# MINI-STM32.net
KiCad netlist of a schematic drawn in Altium Designer
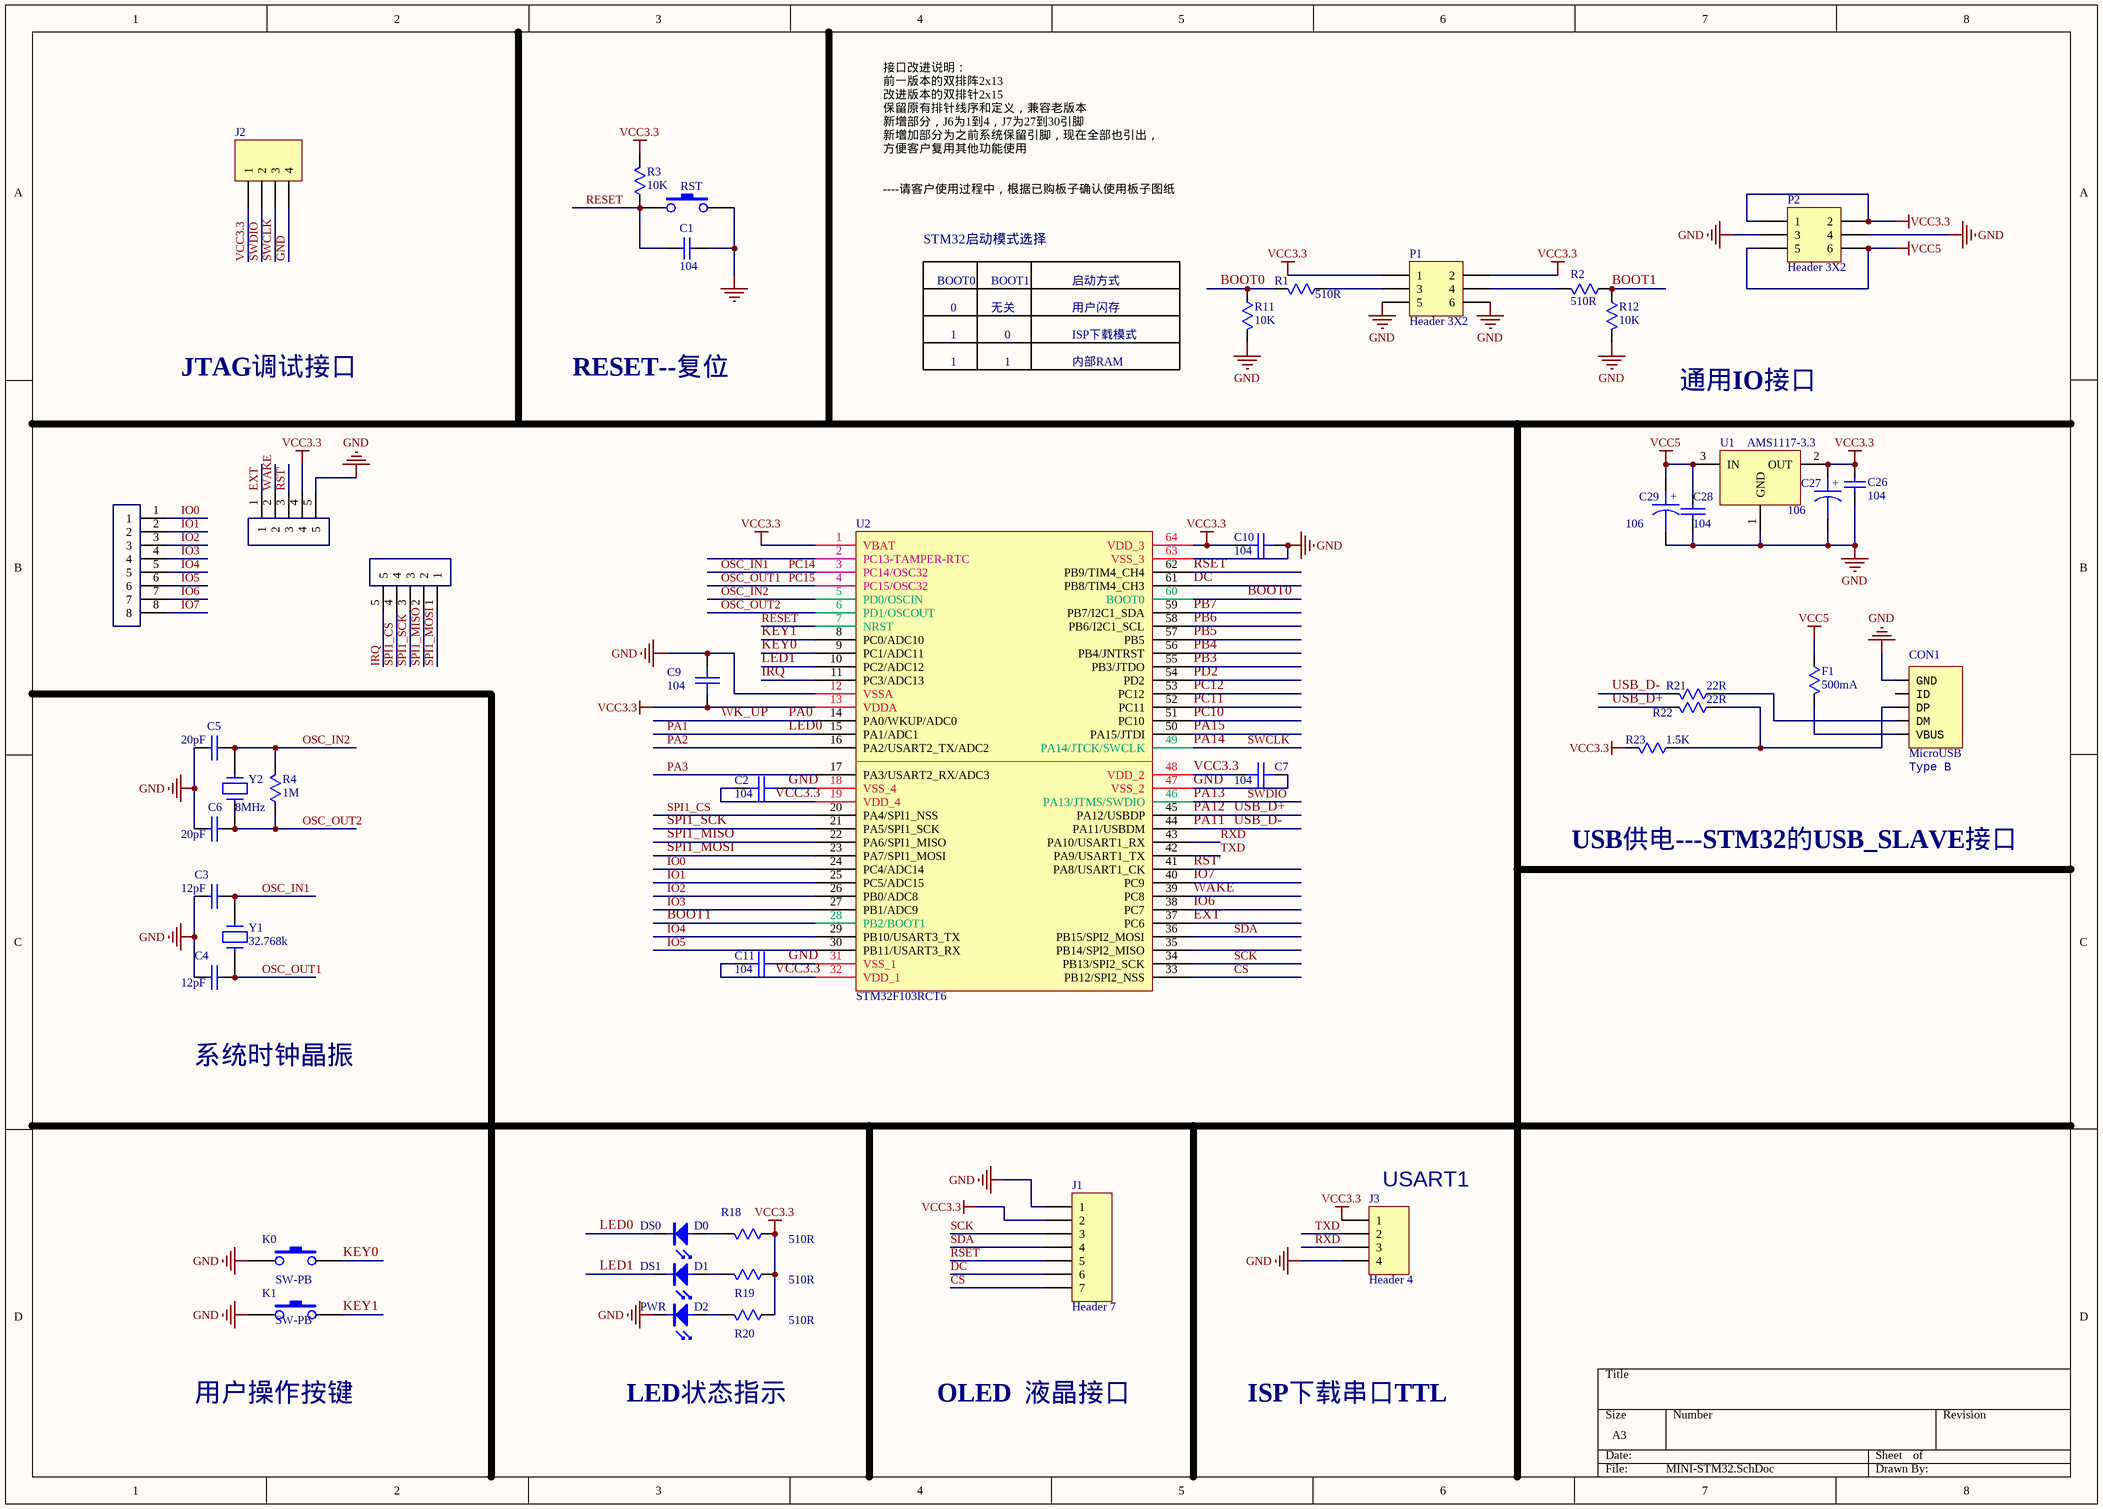
[diagram p0: MINI-STM32.SchDoc]

(export (version "E")
  (design (tool "Eeschema 10.0.6"))
  (components
    (comp (ref "C1")
      (value "104")
      (footprint "0603C")
      (description "GRM39 X7R102K50PT")
      (fields (field (name "PUBLISHER") "Altium Limited"))
      (libsource (lib "") (part "CAP_1"))
    )
    (comp (ref "C2") (value "104") (footprint "0603J") (libsource (lib "YT1_SCH_99SE") (part "CAP")))
    (comp (ref "C3")
      (value "12pF")
      (footprint "0603J")
      (description "CAP CHIP 20P 50V(+-5% C0G 0603)")
      (libsource (lib "Miscellaneous Devices") (part "CAP"))
    )
    (comp (ref "C4")
      (value "12pF")
      (footprint "0603J")
      (description "CAP CHIP 20P 50V(+-5% C0G 0603)")
      (libsource (lib "Miscellaneous Devices") (part "CAP"))
    )
    (comp (ref "C5")
      (value "20pF")
      (footprint "0603J")
      (description "CAP CHIP 20P 50V(+-5% C0G 0603)")
      (libsource (lib "Miscellaneous Devices") (part "CAP"))
    )
    (comp (ref "C6")
      (value "20pF")
      (footprint "0603J")
      (description "CAP CHIP 20P 50V(+-5% C0G 0603)")
      (libsource (lib "Miscellaneous Devices") (part "CAP"))
    )
    (comp (ref "C7") (value "104") (footprint "0603J") (libsource (lib "YT1_SCH_99SE") (part "CAP")))
    (comp (ref "C9") (value "104") (footprint "0603J") (libsource (lib "YT1_SCH_99SE") (part "CAP")))
    (comp (ref "C10") (value "104") (footprint "0603J") (libsource (lib "YT1_SCH_99SE") (part "CAP")))
    (comp (ref "C11") (value "104") (footprint "0603J") (libsource (lib "YT1_SCH_99SE") (part "CAP")))
    (comp (ref "C26")
      (value "104")
      (footprint "0603J")
      (description "Capacitor")
      (fields (field (name "PUBLISHER") "Altium Limited"))
      (libsource (lib "*") (part "Cap"))
    )
    (comp (ref "C27")
      (value "106")
      (footprint "RC0805")
      (description "Capacitor")
      (libsource (lib "*") (part "CAPACITOR POL"))
    )
    (comp (ref "C28")
      (value "104")
      (footprint "0603J")
      (description "Capacitor")
      (libsource (lib "*") (part "CAP"))
    )
    (comp (ref "C29")
      (value "106")
      (footprint "RC0805")
      (description "Capacitor")
      (libsource (lib "*") (part "CAPACITOR POL"))
    )
    (comp (ref "CON1")
      (value "MicroUSB")
      (footprint "PCB_USB:USB_Micro-AB")
      (description "USB")
      (fields (field (name "ALTIUM_VALUE") "Type B"))
      (libsource (lib "SCH_USB") (part "USB_Micro"))
    )
    (comp (ref "D0") (value "DS0") (footprint "LED0805") (libsource (lib "YT1_SCH_99SE") (part "LED")))
    (comp (ref "D1") (value "DS1") (footprint "LED0805") (libsource (lib "YT1_SCH_99SE") (part "LED")))
    (comp (ref "D2") (value "PWR") (footprint "LED0805") (libsource (lib "YT1_SCH_99SE") (part "LED")))
    (comp (ref "F1") (value "500mA") (footprint "RC0805") (libsource (lib "YT1_SCH_99SE") (part "RES")))
    (comp (ref "J1")
      (value "Header 7")
      (footprint "HDR1X7")
      (description "Header, 7-Pin")
      (fields (field (name "PUBLISHER") "Altium Limited"))
      (libsource (lib "Miscellaneous Connectors") (part "Header 7"))
    )
    (comp (ref "J2")
      (value "Header 4")
      (footprint "HDR1X4")
      (description "Header, 4-Pin")
      (fields (field (name "PUBLISHER") "Altium Limited"))
      (libsource (lib "") (part "Header 4_1"))
    )
    (comp (ref "J3")
      (value "Header 4")
      (footprint "HDR1X4")
      (description "Header, 4-Pin")
      (fields (field (name "PUBLISHER") "Altium Limited"))
      (libsource (lib "Miscellaneous Connectors") (part "Header 4"))
    )
    (comp (ref "J090") (value "J1X8") (footprint "HDR1X8") (libsource (lib "GHY原理图库200617") (part "J1X8")))
    (comp (ref "J091") (value "J1X5") (footprint "HDR1X5") (libsource (lib "GHY原理图库200617") (part "J1X5")))
    (comp (ref "J092") (value "J1X5") (footprint "HDR1X5") (libsource (lib "GHY原理图库200617") (part "J1X5")))
    (comp (ref "K0") (value "SW-PB") (footprint "SW-SPST") (libsource (lib "*") (part "SW-PB")))
    (comp (ref "K1") (value "SW-PB") (footprint "SW-SPST") (libsource (lib "*") (part "SW-PB")))
    (comp (ref "P1")
      (value "Header 3X2")
      (footprint "HDR2X3")
      (description "Header, 3-Pin, Dual row")
      (fields (field (name "PUBLISHER") "Altium Limited"))
      (libsource (lib "Miscellaneous Connectors") (part "Header 3X2"))
    )
    (comp (ref "P2")
      (value "Header 3X2")
      (footprint "HDR2X3")
      (description "Header, 3-Pin, Dual row")
      (fields (field (name "PUBLISHER") "Altium Limited"))
      (libsource (lib "Miscellaneous Connectors") (part "Header 3X2"))
    )
    (comp (ref "R1") (value "510R") (footprint "0603J") (libsource (lib "YT1_SCH_99SE") (part "RES")))
    (comp (ref "R2") (value "510R") (footprint "0603J") (libsource (lib "YT1_SCH_99SE") (part "RES")))
    (comp (ref "R3") (value "10K") (footprint "0603J") (libsource (lib "YT1_SCH_99SE") (part "RES")))
    (comp (ref "R4") (value "1M") (footprint "0603J") (libsource (lib "YT1_SCH_99SE") (part "RES")))
    (comp (ref "R11") (value "10K") (footprint "0603J") (libsource (lib "YT1_SCH_99SE") (part "RES")))
    (comp (ref "R12") (value "10K") (footprint "0603J") (libsource (lib "YT1_SCH_99SE") (part "RES")))
    (comp (ref "R18") (value "510R") (footprint "0603J") (libsource (lib "YT1_SCH_99SE") (part "RES")))
    (comp (ref "R19") (value "510R") (footprint "0603J") (libsource (lib "YT1_SCH_99SE") (part "RES")))
    (comp (ref "R20") (value "510R") (footprint "0603J") (libsource (lib "YT1_SCH_99SE") (part "RES")))
    (comp (ref "R21") (value "22R") (footprint "0603J") (libsource (lib "YT1_SCH_99SE") (part "RES")))
    (comp (ref "R22") (value "22R") (footprint "0603") (libsource (lib "YT1_SCH_99SE") (part "RES")))
    (comp (ref "R23") (value "1.5K") (footprint "0603J") (libsource (lib "YT1_SCH_99SE") (part "RES")))
    (comp (ref "RST") (value "~") (footprint "SW-SPST") (libsource (lib "*") (part "SW-PB")))
    (comp (ref "U1")
      (value "AMS1117-3.3")
      (footprint "SOT223")
      (libsource (lib "Newcapec9263_Board_NEW") (part "LT1085CM-3.3"))
    )
    (comp (ref "U2")
      (value "STM32F103RCT6")
      (footprint "LQFP64")
      (libsource (lib "YT1_SCH_99SE") (part "STM32F103RBT6"))
    )
    (comp (ref "Y1")
      (value "32.768k")
      (footprint "32.768k")
      (description "Crystal 8MHz PLUG")
      (libsource (lib "*") (part "CRYSTAL"))
    )
    (comp (ref "Y2")
      (value "8MHz")
      (footprint "smt-xtal")
      (description "Crystal 8MHz PLUG")
      (libsource (lib "*") (part "CRYSTAL"))
    )
  )
  (nets
    (net (code "1") (name "/BOOT0") (class "Default")
      (node (ref "R1") (pin "2") (pinfunction "2_2") (pintype "passive"))
      (node (ref "R11") (pin "1") (pinfunction "1_1") (pintype "passive"))
      (node (ref "U2") (pin "60") (pinfunction "BOOT0_60") (pintype "passive"))
    )
    (net (code "2") (name "/BOOT1") (class "Default")
      (node (ref "R12") (pin "1") (pinfunction "1_1") (pintype "passive"))
      (node (ref "R2") (pin "1") (pinfunction "1_1") (pintype "passive"))
      (node (ref "U2") (pin "28") (pinfunction "PB2/BOOT1_28") (pintype "passive"))
    )
    (net (code "3") (name "/CS") (class "Default")
      (node (ref "J1") (pin "7") (pinfunction "7_7") (pintype "passive"))
      (node (ref "U2") (pin "33") (pinfunction "PB12/SPI2_NSS_33") (pintype "passive"))
    )
    (net (code "4") (name "/DC") (class "Default")
      (node (ref "J1") (pin "6") (pinfunction "6_6") (pintype "passive"))
      (node (ref "U2") (pin "61") (pinfunction "PB8/TIM4_CH3_61") (pintype "passive"))
    )
    (net (code "5") (name "/EXT") (class "Default")
      (node (ref "J091") (pin "1") (pinfunction "1_1") (pintype "passive"))
      (node (ref "U2") (pin "37") (pinfunction "PC6_37") (pintype "passive"))
    )
    (net (code "6") (name "/IO0") (class "Default")
      (node (ref "J090") (pin "1") (pinfunction "1_1") (pintype "passive"))
      (node (ref "U2") (pin "24") (pinfunction "PC4/ADC14_24") (pintype "passive"))
    )
    (net (code "7") (name "/IO1") (class "Default")
      (node (ref "J090") (pin "2") (pinfunction "2_2") (pintype "passive"))
      (node (ref "U2") (pin "25") (pinfunction "PC5/ADC15_25") (pintype "passive"))
    )
    (net (code "8") (name "/IO2") (class "Default")
      (node (ref "J090") (pin "3") (pinfunction "3_3") (pintype "passive"))
      (node (ref "U2") (pin "26") (pinfunction "PB0/ADC8_26") (pintype "passive"))
    )
    (net (code "9") (name "/IO3") (class "Default")
      (node (ref "J090") (pin "4") (pinfunction "4_4") (pintype "passive"))
      (node (ref "U2") (pin "27") (pinfunction "PB1/ADC9_27") (pintype "passive"))
    )
    (net (code "10") (name "/IO4") (class "Default")
      (node (ref "J090") (pin "5") (pinfunction "5_5") (pintype "passive"))
      (node (ref "U2") (pin "29") (pinfunction "PB10/USART3_TX_29") (pintype "passive"))
    )
    (net (code "11") (name "/IO5") (class "Default")
      (node (ref "J090") (pin "6") (pinfunction "6_6") (pintype "passive"))
      (node (ref "U2") (pin "30") (pinfunction "PB11/USART3_RX_30") (pintype "passive"))
    )
    (net (code "12") (name "/IO6") (class "Default")
      (node (ref "J090") (pin "7") (pinfunction "7_7") (pintype "passive"))
      (node (ref "U2") (pin "38") (pinfunction "PC7_38") (pintype "passive"))
    )
    (net (code "13") (name "/IO7") (class "Default")
      (node (ref "J090") (pin "8") (pinfunction "8_8") (pintype "passive"))
      (node (ref "U2") (pin "40") (pinfunction "PC9_40") (pintype "passive"))
    )
    (net (code "14") (name "/IRQ") (class "Default")
      (node (ref "J092") (pin "5") (pinfunction "5_5") (pintype "passive"))
      (node (ref "U2") (pin "11") (pinfunction "PC3/ADC13_11") (pintype "passive"))
    )
    (net (code "15") (name "/KEY0") (class "Default")
      (node (ref "K0") (pin "2") (pinfunction "2_2") (pintype "passive"))
      (node (ref "U2") (pin "9") (pinfunction "PC1/ADC11_9") (pintype "passive"))
    )
    (net (code "16") (name "/KEY1") (class "Default")
      (node (ref "K1") (pin "2") (pinfunction "2_2") (pintype "passive"))
      (node (ref "U2") (pin "8") (pinfunction "PC0/ADC10_8") (pintype "passive"))
    )
    (net (code "17") (name "/LED0") (class "Default")
      (node (ref "D0") (pin "2") (pinfunction "2_2") (pintype "passive"))
      (node (ref "U2") (pin "15") (pinfunction "PA1/ADC1_15") (pintype "passive"))
    )
    (net (code "18") (name "/LED1") (class "Default")
      (node (ref "D1") (pin "2") (pinfunction "2_2") (pintype "passive"))
      (node (ref "U2") (pin "10") (pinfunction "PC2/ADC12_10") (pintype "passive"))
    )
    (net (code "19") (name "/OSC_IN1") (class "Default")
      (node (ref "C3") (pin "2") (pinfunction "2_2") (pintype "passive"))
      (node (ref "U2") (pin "3") (pinfunction "PC14/OSC32_3") (pintype "passive"))
      (node (ref "Y1") (pin "2") (pinfunction "2_2") (pintype "passive"))
    )
    (net (code "20") (name "/OSC_IN2") (class "Default")
      (node (ref "C5") (pin "2") (pinfunction "2_2") (pintype "passive"))
      (node (ref "R4") (pin "2") (pinfunction "2_2") (pintype "passive"))
      (node (ref "U2") (pin "5") (pinfunction "PD0/OSCIN_5") (pintype "passive"))
      (node (ref "Y2") (pin "1") (pinfunction "1_1") (pintype "passive"))
    )
    (net (code "21") (name "/OSC_OUT1") (class "Default")
      (node (ref "C4") (pin "2") (pinfunction "2_2") (pintype "passive"))
      (node (ref "U2") (pin "4") (pinfunction "PC15/OSC32_4") (pintype "passive"))
      (node (ref "Y1") (pin "1") (pinfunction "1_1") (pintype "passive"))
    )
    (net (code "22") (name "/OSC_OUT2") (class "Default")
      (node (ref "C6") (pin "2") (pinfunction "2_2") (pintype "passive"))
      (node (ref "R4") (pin "1") (pinfunction "1_1") (pintype "passive"))
      (node (ref "U2") (pin "6") (pinfunction "PD1/OSCOUT_6") (pintype "passive"))
      (node (ref "Y2") (pin "2") (pinfunction "2_2") (pintype "passive"))
    )
    (net (code "23") (name "/PA0") (class "Default")
      (node (ref "U2") (pin "14") (pinfunction "PA0/WKUP/ADC0_14") (pintype "passive"))
    )
    (net (code "24") (name "/PA2") (class "Default")
      (node (ref "U2") (pin "16") (pinfunction "PA2/USART2_TX/ADC2_16") (pintype "passive"))
    )
    (net (code "25") (name "/PA3") (class "Default")
      (node (ref "U2") (pin "17") (pinfunction "PA3/USART2_RX/ADC3_17") (pintype "passive"))
    )
    (net (code "26") (name "/PA11") (class "Default")
      (node (ref "R21") (pin "2") (pinfunction "2_2") (pintype "passive"))
      (node (ref "U2") (pin "44") (pinfunction "PA11/USBDM_44") (pintype "passive"))
    )
    (net (code "27") (name "/PA12") (class "Default")
      (node (ref "R22") (pin "2") (pinfunction "2_2") (pintype "passive"))
      (node (ref "U2") (pin "45") (pinfunction "PA12/USBDP_45") (pintype "passive"))
    )
    (net (code "28") (name "/PA13") (class "Default")
      (node (ref "J2") (pin "2") (pinfunction "2_2") (pintype "passive"))
      (node (ref "U2") (pin "46") (pinfunction "PA13/JTMS/SWDIO_46") (pintype "passive"))
    )
    (net (code "29") (name "/PA14") (class "Default")
      (node (ref "J2") (pin "3") (pinfunction "3_3") (pintype "passive"))
      (node (ref "U2") (pin "49") (pinfunction "PA14/JTCK/SWCLK_49") (pintype "passive"))
    )
    (net (code "30") (name "/PA15") (class "Default")
      (node (ref "U2") (pin "50") (pinfunction "PA15/JTDI_50") (pintype "passive"))
    )
    (net (code "31") (name "/PB3") (class "Default")
      (node (ref "U2") (pin "55") (pinfunction "PB3/JTDO_55") (pintype "passive"))
    )
    (net (code "32") (name "/PB4") (class "Default")
      (node (ref "U2") (pin "56") (pinfunction "PB4/JNTRST_56") (pintype "passive"))
    )
    (net (code "33") (name "/PB5") (class "Default")
      (node (ref "U2") (pin "57") (pinfunction "PB5_57") (pintype "passive"))
    )
    (net (code "34") (name "/PB6") (class "Default")
      (node (ref "U2") (pin "58") (pinfunction "PB6/I2C1_SCL_58") (pintype "passive"))
    )
    (net (code "35") (name "/PB7") (class "Default")
      (node (ref "U2") (pin "59") (pinfunction "PB7/I2C1_SDA_59") (pintype "passive"))
    )
    (net (code "36") (name "/PC10") (class "Default")
      (node (ref "U2") (pin "51") (pinfunction "PC10_51") (pintype "passive"))
    )
    (net (code "37") (name "/PC11") (class "Default")
      (node (ref "U2") (pin "52") (pinfunction "PC11_52") (pintype "passive"))
    )
    (net (code "38") (name "/PC12") (class "Default")
      (node (ref "U2") (pin "53") (pinfunction "PC12_53") (pintype "passive"))
    )
    (net (code "39") (name "/PD2") (class "Default")
      (node (ref "U2") (pin "54") (pinfunction "PD2_54") (pintype "passive"))
    )
    (net (code "40") (name "/RESET") (class "Default")
      (node (ref "C1") (pin "2") (pinfunction "2_2") (pintype "passive"))
      (node (ref "R3") (pin "1") (pinfunction "1_1") (pintype "passive"))
      (node (ref "RST") (pin "1") (pinfunction "1_1") (pintype "passive"))
      (node (ref "U2") (pin "7") (pinfunction "NRST_7") (pintype "passive"))
    )
    (net (code "41") (name "/RSET") (class "Default")
      (node (ref "J1") (pin "5") (pinfunction "5_5") (pintype "passive"))
      (node (ref "U2") (pin "62") (pinfunction "PB9/TIM4_CH4_62") (pintype "passive"))
    )
    (net (code "42") (name "/RST'") (class "Default")
      (node (ref "J091") (pin "3") (pinfunction "3_3") (pintype "passive"))
      (node (ref "U2") (pin "41") (pinfunction "PA8/USART1_CK_41") (pintype "passive"))
    )
    (net (code "43") (name "/RXD") (class "Default")
      (node (ref "J3") (pin "3") (pinfunction "3_3") (pintype "passive"))
      (node (ref "U2") (pin "43") (pinfunction "PA10/USART1_RX_43") (pintype "passive"))
    )
    (net (code "44") (name "/SCK") (class "Default")
      (node (ref "J1") (pin "3") (pinfunction "3_3") (pintype "passive"))
      (node (ref "U2") (pin "34") (pinfunction "PB13/SPI2_SCK_34") (pintype "passive"))
    )
    (net (code "45") (name "/SDA") (class "Default")
      (node (ref "J1") (pin "4") (pinfunction "4_4") (pintype "passive"))
      (node (ref "U2") (pin "36") (pinfunction "PB15/SPI2_MOSI_36") (pintype "passive"))
    )
    (net (code "46") (name "/SPI1_CS") (class "Default")
      (node (ref "J092") (pin "4") (pinfunction "4_4") (pintype "passive"))
      (node (ref "U2") (pin "20") (pinfunction "PA4/SPI1_NSS_20") (pintype "passive"))
    )
    (net (code "47") (name "/SPI1_MISO") (class "Default")
      (node (ref "J092") (pin "2") (pinfunction "2_2") (pintype "passive"))
      (node (ref "U2") (pin "22") (pinfunction "PA6/SPI1_MISO_22") (pintype "passive"))
    )
    (net (code "48") (name "/SPI1_MOSI") (class "Default")
      (node (ref "J092") (pin "1") (pinfunction "1_1") (pintype "passive"))
      (node (ref "U2") (pin "23") (pinfunction "PA7/SPI1_MOSI_23") (pintype "passive"))
    )
    (net (code "49") (name "/SPI1_SCK") (class "Default")
      (node (ref "J092") (pin "3") (pinfunction "3_3") (pintype "passive"))
      (node (ref "U2") (pin "21") (pinfunction "PA5/SPI1_SCK_21") (pintype "passive"))
    )
    (net (code "50") (name "/TXD") (class "Default")
      (node (ref "J3") (pin "2") (pinfunction "2_2") (pintype "passive"))
      (node (ref "U2") (pin "42") (pinfunction "PA9/USART1_TX_42") (pintype "passive"))
    )
    (net (code "51") (name "/WAKE") (class "Default")
      (node (ref "J091") (pin "2") (pinfunction "2_2") (pintype "passive"))
      (node (ref "U2") (pin "39") (pinfunction "PC8_39") (pintype "passive"))
    )
    (net (code "52") (name "GND") (class "Default")
      (node (ref "C1") (pin "1") (pinfunction "1_1") (pintype "passive"))
      (node (ref "C10") (pin "2") (pinfunction "2_2") (pintype "passive"))
      (node (ref "C11") (pin "2") (pinfunction "2_2") (pintype "passive"))
      (node (ref "C2") (pin "2") (pinfunction "2_2") (pintype "passive"))
      (node (ref "C26") (pin "2") (pinfunction "2_2") (pintype "passive"))
      (node (ref "C27") (pin "2") (pinfunction "2_2") (pintype "passive"))
      (node (ref "C28") (pin "2") (pinfunction "2_2") (pintype "passive"))
      (node (ref "C29") (pin "2") (pinfunction "2_2") (pintype "passive"))
      (node (ref "C3") (pin "1") (pinfunction "1_1") (pintype "passive"))
      (node (ref "C4") (pin "1") (pinfunction "1_1") (pintype "passive"))
      (node (ref "C5") (pin "1") (pinfunction "1_1") (pintype "passive"))
      (node (ref "C6") (pin "1") (pinfunction "1_1") (pintype "passive"))
      (node (ref "C7") (pin "2") (pinfunction "2_2") (pintype "passive"))
      (node (ref "C9") (pin "1") (pinfunction "1_1") (pintype "passive"))
      (node (ref "CON1") (pin "5") (pinfunction "GND_5") (pintype "passive"))
      (node (ref "D2") (pin "2") (pinfunction "2_2") (pintype "passive"))
      (node (ref "J091") (pin "5") (pinfunction "5_5") (pintype "passive"))
      (node (ref "J1") (pin "1") (pinfunction "1_1") (pintype "passive"))
      (node (ref "J2") (pin "4") (pinfunction "4_4") (pintype "passive"))
      (node (ref "J3") (pin "4") (pinfunction "4_4") (pintype "passive"))
      (node (ref "K0") (pin "1") (pinfunction "1_1") (pintype "passive"))
      (node (ref "K1") (pin "1") (pinfunction "1_1") (pintype "passive"))
      (node (ref "P1") (pin "5") (pinfunction "5_5") (pintype "passive"))
      (node (ref "P1") (pin "6") (pinfunction "6_6") (pintype "passive"))
      (node (ref "P2") (pin "3") (pinfunction "3_3") (pintype "passive"))
      (node (ref "P2") (pin "4") (pinfunction "4_4") (pintype "passive"))
      (node (ref "R11") (pin "2") (pinfunction "2_2") (pintype "passive"))
      (node (ref "R12") (pin "2") (pinfunction "2_2") (pintype "passive"))
      (node (ref "RST") (pin "2") (pinfunction "2_2") (pintype "passive"))
      (node (ref "U1") (pin "1") (pinfunction "GND_1") (pintype "passive"))
      (node (ref "U2") (pin "12") (pinfunction "VSSA_12") (pintype "passive"))
      (node (ref "U2") (pin "18") (pinfunction "VSS_4_18") (pintype "passive"))
      (node (ref "U2") (pin "31") (pinfunction "VSS_1_31") (pintype "passive"))
      (node (ref "U2") (pin "47") (pinfunction "VSS_2_47") (pintype "passive"))
      (node (ref "U2") (pin "63") (pinfunction "VSS_3_63") (pintype "passive"))
    )
    (net (code "53") (name "Net-(CON1-DM)") (class "Default")
      (node (ref "CON1") (pin "2") (pinfunction "DM_2") (pintype "passive"))
      (node (ref "R21") (pin "1") (pinfunction "1_1") (pintype "passive"))
    )
    (net (code "54") (name "Net-(CON1-DP)") (class "Default")
      (node (ref "CON1") (pin "3") (pinfunction "DP_3") (pintype "passive"))
      (node (ref "R22") (pin "1") (pinfunction "1_1") (pintype "passive"))
      (node (ref "R23") (pin "1") (pinfunction "1_1") (pintype "passive"))
    )
    (net (code "55") (name "Net-(CON1-VBUS)") (class "Default")
      (node (ref "CON1") (pin "1") (pinfunction "VBUS_1") (pintype "passive"))
      (node (ref "F1") (pin "2") (pinfunction "2_2") (pintype "passive"))
    )
    (net (code "56") (name "Net-(D0-Pad1)") (class "Default")
      (node (ref "D0") (pin "1") (pinfunction "1_1") (pintype "passive"))
      (node (ref "R18") (pin "2") (pinfunction "2_2") (pintype "passive"))
    )
    (net (code "57") (name "Net-(D1-Pad1)") (class "Default")
      (node (ref "D1") (pin "1") (pinfunction "1_1") (pintype "passive"))
      (node (ref "R19") (pin "2") (pinfunction "2_2") (pintype "passive"))
    )
    (net (code "58") (name "Net-(D2-Pad1)") (class "Default")
      (node (ref "D2") (pin "1") (pinfunction "1_1") (pintype "passive"))
      (node (ref "R20") (pin "2") (pinfunction "2_2") (pintype "passive"))
    )
    (net (code "59") (name "Net-(P1-Pad3)") (class "Default")
      (node (ref "P1") (pin "3") (pinfunction "3_3") (pintype "passive"))
      (node (ref "R1") (pin "1") (pinfunction "1_1") (pintype "passive"))
    )
    (net (code "60") (name "Net-(P1-Pad4)") (class "Default")
      (node (ref "P1") (pin "4") (pinfunction "4_4") (pintype "passive"))
      (node (ref "R2") (pin "2") (pinfunction "2_2") (pintype "passive"))
    )
    (net (code "61") (name "VCC3.3") (class "Default")
      (node (ref "C10") (pin "1") (pinfunction "1_1") (pintype "passive"))
      (node (ref "C11") (pin "1") (pinfunction "1_1") (pintype "passive"))
      (node (ref "C2") (pin "1") (pinfunction "1_1") (pintype "passive"))
      (node (ref "C26") (pin "1") (pinfunction "1_1") (pintype "passive"))
      (node (ref "C27") (pin "1") (pinfunction "1_1") (pintype "passive"))
      (node (ref "C7") (pin "1") (pinfunction "1_1") (pintype "passive"))
      (node (ref "C9") (pin "2") (pinfunction "2_2") (pintype "passive"))
      (node (ref "J091") (pin "4") (pinfunction "4_4") (pintype "passive"))
      (node (ref "J1") (pin "2") (pinfunction "2_2") (pintype "passive"))
      (node (ref "J2") (pin "1") (pinfunction "1_1") (pintype "passive"))
      (node (ref "J3") (pin "1") (pinfunction "1_1") (pintype "passive"))
      (node (ref "P1") (pin "1") (pinfunction "1_1") (pintype "passive"))
      (node (ref "P1") (pin "2") (pinfunction "2_2") (pintype "passive"))
      (node (ref "P2") (pin "1") (pinfunction "1_1") (pintype "passive"))
      (node (ref "P2") (pin "2") (pinfunction "2_2") (pintype "passive"))
      (node (ref "R18") (pin "1") (pinfunction "1_1") (pintype "passive"))
      (node (ref "R19") (pin "1") (pinfunction "1_1") (pintype "passive"))
      (node (ref "R20") (pin "1") (pinfunction "1_1") (pintype "passive"))
      (node (ref "R23") (pin "2") (pinfunction "2_2") (pintype "passive"))
      (node (ref "R3") (pin "2") (pinfunction "2_2") (pintype "passive"))
      (node (ref "U1") (pin "2") (pinfunction "OUT_2") (pintype "passive"))
      (node (ref "U2") (pin "1") (pinfunction "VBAT_1") (pintype "passive"))
      (node (ref "U2") (pin "13") (pinfunction "VDDA_13") (pintype "passive"))
      (node (ref "U2") (pin "19") (pinfunction "VDD_4_19") (pintype "passive"))
      (node (ref "U2") (pin "32") (pinfunction "VDD_1_32") (pintype "passive"))
      (node (ref "U2") (pin "48") (pinfunction "VDD_2_48") (pintype "passive"))
      (node (ref "U2") (pin "64") (pinfunction "VDD_3_64") (pintype "passive"))
    )
    (net (code "62") (name "VCC5") (class "Default")
      (node (ref "C28") (pin "1") (pinfunction "1_1") (pintype "passive"))
      (node (ref "C29") (pin "1") (pinfunction "1_1") (pintype "passive"))
      (node (ref "F1") (pin "1") (pinfunction "1_1") (pintype "passive"))
      (node (ref "P2") (pin "5") (pinfunction "5_5") (pintype "passive"))
      (node (ref "P2") (pin "6") (pinfunction "6_6") (pintype "passive"))
      (node (ref "U1") (pin "3") (pinfunction "IN_3") (pintype "passive"))
    )
    (net (code "63") (name "unconnected-(CON1-ID-Pad4)") (class "Default")
      (node (ref "CON1") (pin "4") (pinfunction "ID_4") (pintype "passive"))
    )
    (net (code "64") (name "unconnected-(CON1-SH-Pad0)") (class "Default")
      (node (ref "CON1") (pin "0") (pinfunction "SH_0") (pintype "passive"))
    )
    (net (code "65") (name "unconnected-(U2-PB14{slash}SPI2_MISO-Pad35)") (class "Default")
      (node (ref "U2") (pin "35") (pinfunction "PB14/SPI2_MISO_35") (pintype "passive"))
    )
    (net (code "66") (name "unconnected-(U2-PC13-TAMPER-RTC-Pad2)") (class "Default")
      (node (ref "U2") (pin "2") (pinfunction "PC13-TAMPER-RTC_2") (pintype "passive"))
    )
  )
)
